# USB_UART_PSU_SCH.net
KiCad netlist of a schematic drawn in Altium Designer
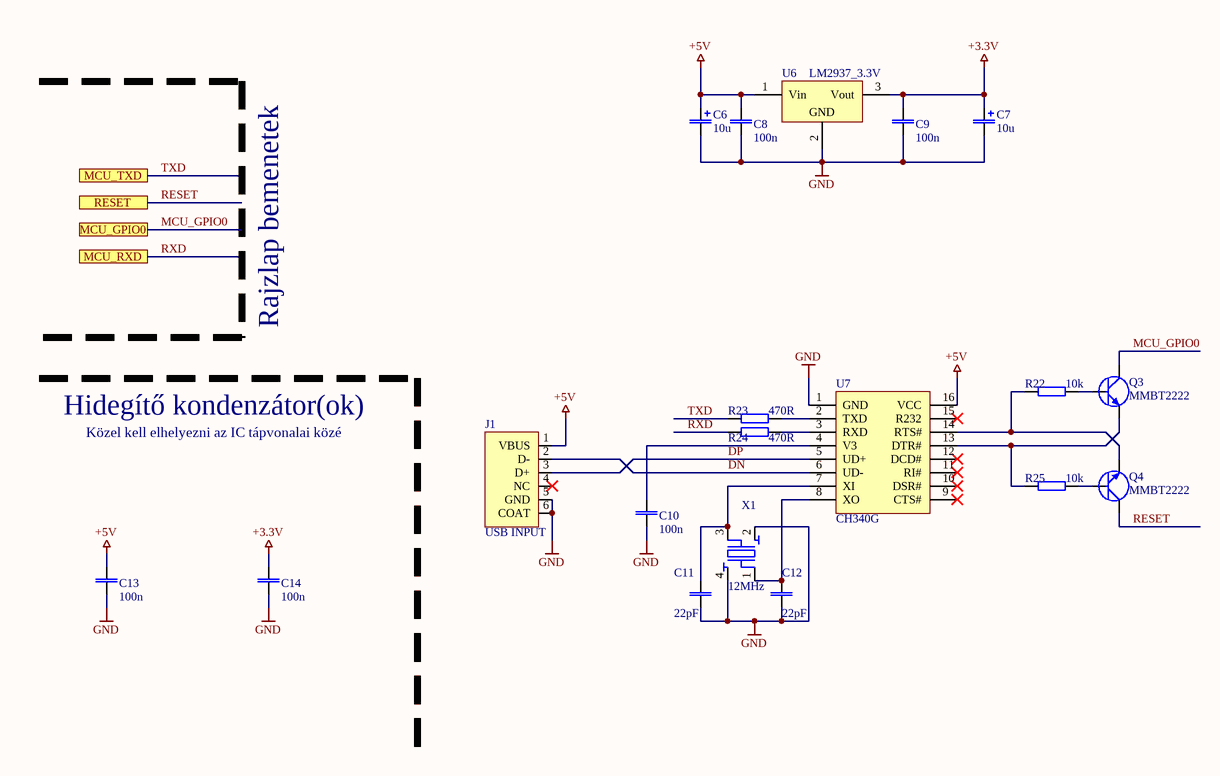
[diagram p0: USB_UART_PSU_SCH.SchDoc]

(export (version "E")
  (design (tool "Eeschema 10.0.6"))
  (components
    (comp (ref "C6")
      (value "10u")
      (footprint "CAP 1210")
      (description "POLARIZED CAPACITOR")
      (libsource (lib "SCH_LIB") (part "CAP_POL"))
    )
    (comp (ref "C7")
      (value "10u")
      (footprint "CAP 1210")
      (description "POLARIZED CAPACITOR")
      (libsource (lib "SCH_LIB") (part "CAP_POL"))
    )
    (comp (ref "C8")
      (value "100n")
      (footprint "CAP 0805")
      (description "NON POLARIZED CAPACITOR")
      (libsource (lib "SCH_LIB") (part "CAP"))
    )
    (comp (ref "C9")
      (value "100n")
      (footprint "CAP 0805")
      (description "NON POLARIZED CAPACITOR")
      (libsource (lib "SCH_LIB") (part "CAP"))
    )
    (comp (ref "C10")
      (value "100n")
      (footprint "CAP 0805")
      (description "NON POLARIZED CAPACITOR")
      (libsource (lib "SCH_LIB") (part "CAP"))
    )
    (comp (ref "C11")
      (value "22pF")
      (footprint "CAP 0805")
      (description "NON POLARIZED CAPACITOR")
      (libsource (lib "SCH_LIB") (part "CAP"))
    )
    (comp (ref "C12")
      (value "22pF")
      (footprint "CAP 0805")
      (description "NON POLARIZED CAPACITOR")
      (libsource (lib "SCH_LIB") (part "CAP"))
    )
    (comp (ref "C13")
      (value "100n")
      (footprint "CAP 0805")
      (description "NON POLARIZED CAPACITOR")
      (libsource (lib "SCH_LIB") (part "CAP"))
    )
    (comp (ref "C14")
      (value "100n")
      (footprint "CAP 0805")
      (description "NON POLARIZED CAPACITOR")
      (libsource (lib "SCH_LIB") (part "CAP"))
    )
    (comp (ref "J1")
      (value "USB INPUT")
      (footprint "MUSB-B2.0S05PFHSB-T")
      (description "5PIN miniUSB SMD connector")
      (libsource (lib "SCH_LIB") (part "USB_5PIN"))
    )
    (comp (ref "Q3")
      (value "MMBT2222")
      (footprint "SOT23")
      (description "NPN transistor, SO23")
      (libsource (lib "SCH_LIB") (part "MMBT2222"))
    )
    (comp (ref "Q4")
      (value "MMBT2222")
      (footprint "SOT23")
      (description "NPN transistor, SO23")
      (libsource (lib "SCH_LIB") (part "MMBT2222"))
    )
    (comp (ref "R22")
      (value "10k")
      (footprint "RES 0805")
      (description "RESISTOR")
      (libsource (lib "SCH_LIB") (part "RES"))
    )
    (comp (ref "R23")
      (value "470R")
      (footprint "RES 0805")
      (description "RESISTOR")
      (libsource (lib "SCH_LIB") (part "RES"))
    )
    (comp (ref "R24")
      (value "470R")
      (footprint "RES 0805")
      (description "RESISTOR")
      (libsource (lib "SCH_LIB") (part "RES"))
    )
    (comp (ref "R25")
      (value "10k")
      (footprint "RES 0805")
      (description "RESISTOR")
      (libsource (lib "SCH_LIB") (part "RES"))
    )
    (comp (ref "U6")
      (value "LM2937_3.3V")
      (footprint "SOT223")
      (description "SOT223")
      (libsource (lib "SCH_LIB") (part "LM2937"))
    )
    (comp (ref "U7")
      (value "CH340G")
      (footprint "SO16")
      (description "USB to UART")
      (libsource (lib "SCH_LIB") (part "CH340G"))
    )
    (comp (ref "X1")
      (value "12MHz")
      (footprint "SMD_QUARTZ")
      (description "QUARTZ CRYSTAL")
      (libsource (lib "SCH_LIB") (part "QUARTZ"))
    )
  )
  (nets
    (net (code "1") (name "+3.3V") (class "Default")
      (node (ref "C14") (pin "2") (pinfunction "2_2") (pintype "passive"))
      (node (ref "C7") (pin "1") (pinfunction "+_1") (pintype "passive"))
      (node (ref "C9") (pin "2") (pinfunction "2_2") (pintype "passive"))
      (node (ref "U6") (pin "3") (pinfunction "Vout_3") (pintype "passive"))
    )
    (net (code "2") (name "+5V") (class "Default")
      (node (ref "C13") (pin "2") (pinfunction "2_2") (pintype "passive"))
      (node (ref "C6") (pin "1") (pinfunction "+_1") (pintype "passive"))
      (node (ref "C8") (pin "2") (pinfunction "2_2") (pintype "passive"))
      (node (ref "J1") (pin "1") (pinfunction "VBUS_1") (pintype "passive"))
      (node (ref "U6") (pin "1") (pinfunction "Vin_1") (pintype "passive"))
      (node (ref "U7") (pin "16") (pinfunction "VCC_16") (pintype "passive"))
    )
    (net (code "3") (name "/DN") (class "Default")
      (node (ref "J1") (pin "2") (pinfunction "D-_2") (pintype "passive"))
      (node (ref "U7") (pin "6") (pinfunction "UD-_6") (pintype "passive"))
    )
    (net (code "4") (name "/DP") (class "Default")
      (node (ref "J1") (pin "3") (pinfunction "D+_3") (pintype "passive"))
      (node (ref "U7") (pin "5") (pinfunction "UD+_5") (pintype "passive"))
    )
    (net (code "5") (name "/MCU_GPIO0") (class "Default")
      (node (ref "Q3") (pin "3") (pinfunction "C_3") (pintype "passive"))
    )
    (net (code "6") (name "/RESET") (class "Default")
      (node (ref "Q4") (pin "3") (pinfunction "C_3") (pintype "passive"))
    )
    (net (code "7") (name "/RXD") (class "Default")
      (node (ref "R24") (pin "1") (pinfunction "1_1") (pintype "passive"))
    )
    (net (code "8") (name "/TXD") (class "Default")
      (node (ref "R23") (pin "1") (pinfunction "1_1") (pintype "passive"))
    )
    (net (code "9") (name "GND") (class "Default")
      (node (ref "C10") (pin "2") (pinfunction "2_2") (pintype "passive"))
      (node (ref "C11") (pin "2") (pinfunction "2_2") (pintype "passive"))
      (node (ref "C12") (pin "2") (pinfunction "2_2") (pintype "passive"))
      (node (ref "C13") (pin "1") (pinfunction "1_1") (pintype "passive"))
      (node (ref "C14") (pin "1") (pinfunction "1_1") (pintype "passive"))
      (node (ref "C6") (pin "2") (pinfunction "-_2") (pintype "passive"))
      (node (ref "C7") (pin "2") (pinfunction "-_2") (pintype "passive"))
      (node (ref "C8") (pin "1") (pinfunction "1_1") (pintype "passive"))
      (node (ref "C9") (pin "1") (pinfunction "1_1") (pintype "passive"))
      (node (ref "J1") (pin "5") (pinfunction "GND_5") (pintype "passive"))
      (node (ref "J1") (pin "6") (pinfunction "COAT_6") (pintype "passive"))
      (node (ref "U6") (pin "2") (pinfunction "GND_2") (pintype "passive"))
      (node (ref "U7") (pin "1") (pinfunction "GND_1") (pintype "passive"))
      (node (ref "X1") (pin "2") (pinfunction "GND_2") (pintype "passive"))
      (node (ref "X1") (pin "4") (pinfunction "GND_4") (pintype "passive"))
    )
    (net (code "10") (name "Net-(Q3-B)") (class "Default")
      (node (ref "Q3") (pin "1") (pinfunction "B_1") (pintype "passive"))
      (node (ref "R22") (pin "2") (pinfunction "2_2") (pintype "passive"))
    )
    (net (code "11") (name "Net-(Q3-E)") (class "Default")
      (node (ref "Q3") (pin "2") (pinfunction "E_2") (pintype "passive"))
      (node (ref "R25") (pin "1") (pinfunction "1_1") (pintype "passive"))
      (node (ref "U7") (pin "13") (pinfunction "DTR#_13") (pintype "passive"))
    )
    (net (code "12") (name "Net-(Q4-B)") (class "Default")
      (node (ref "Q4") (pin "1") (pinfunction "B_1") (pintype "passive"))
      (node (ref "R25") (pin "2") (pinfunction "2_2") (pintype "passive"))
    )
    (net (code "13") (name "Net-(Q4-E)") (class "Default")
      (node (ref "Q4") (pin "2") (pinfunction "E_2") (pintype "passive"))
      (node (ref "R22") (pin "1") (pinfunction "1_1") (pintype "passive"))
      (node (ref "U7") (pin "14") (pinfunction "RTS#_14") (pintype "passive"))
    )
    (net (code "14") (name "Net-(U7-RXD)") (class "Default")
      (node (ref "R24") (pin "2") (pinfunction "2_2") (pintype "passive"))
      (node (ref "U7") (pin "3") (pinfunction "RXD_3") (pintype "passive"))
    )
    (net (code "15") (name "Net-(U7-TXD)") (class "Default")
      (node (ref "R23") (pin "2") (pinfunction "2_2") (pintype "passive"))
      (node (ref "U7") (pin "2") (pinfunction "TXD_2") (pintype "passive"))
    )
    (net (code "16") (name "Net-(U7-V3)") (class "Default")
      (node (ref "C10") (pin "1") (pinfunction "1_1") (pintype "passive"))
      (node (ref "U7") (pin "4") (pinfunction "V3_4") (pintype "passive"))
    )
    (net (code "17") (name "Net-(U7-XI)") (class "Default")
      (node (ref "C11") (pin "1") (pinfunction "1_1") (pintype "passive"))
      (node (ref "U7") (pin "7") (pinfunction "XI_7") (pintype "passive"))
      (node (ref "X1") (pin "3") (pinfunction "3_3") (pintype "passive"))
    )
    (net (code "18") (name "Net-(U7-XO)") (class "Default")
      (node (ref "C12") (pin "1") (pinfunction "1_1") (pintype "passive"))
      (node (ref "U7") (pin "8") (pinfunction "XO_8") (pintype "passive"))
      (node (ref "X1") (pin "1") (pinfunction "1_1") (pintype "passive"))
    )
    (net (code "19") (name "unconnected-(J1-NC-Pad4)") (class "Default")
      (node (ref "J1") (pin "4") (pinfunction "NC_4") (pintype "passive+no_connect"))
    )
    (net (code "20") (name "unconnected-(U7-CTS#-Pad9)") (class "Default")
      (node (ref "U7") (pin "9") (pinfunction "CTS#_9") (pintype "passive+no_connect"))
    )
    (net (code "21") (name "unconnected-(U7-DCD#-Pad12)") (class "Default")
      (node (ref "U7") (pin "12") (pinfunction "DCD#_12") (pintype "passive+no_connect"))
    )
    (net (code "22") (name "unconnected-(U7-DSR#-Pad10)") (class "Default")
      (node (ref "U7") (pin "10") (pinfunction "DSR#_10") (pintype "passive+no_connect"))
    )
    (net (code "23") (name "unconnected-(U7-R232-Pad15)") (class "Default")
      (node (ref "U7") (pin "15") (pinfunction "R232_15") (pintype "passive+no_connect"))
    )
    (net (code "24") (name "unconnected-(U7-RI#-Pad11)") (class "Default")
      (node (ref "U7") (pin "11") (pinfunction "RI#_11") (pintype "passive+no_connect"))
    )
  )
)
